# bluetooth.net
KiCad netlist of a schematic drawn in Altium Designer
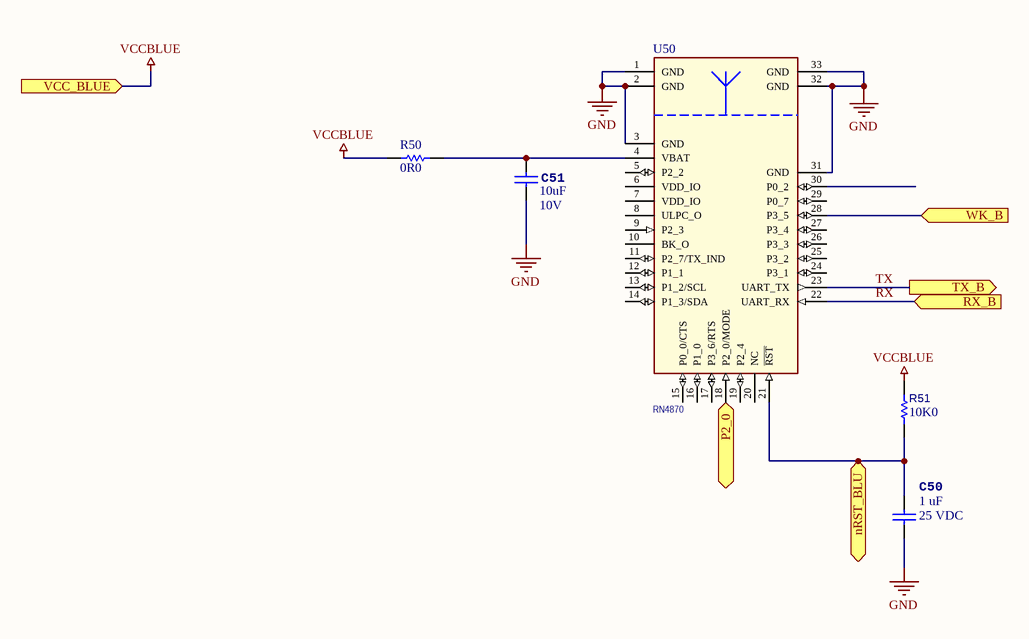
[diagram p0: bluetooth.SchDoc]

(export (version "E")
  (design (tool "Eeschema 10.0.6"))
  (components
    (comp (ref "C50")
      (value "1uF, 25V")
      (footprint "C0603")
      (description "Cap_Cer")
      (fields
        (field (name "MANUFACTURER") "Taiyo Yuden")
        (field (name "MANUFACTURER PART NUMBER") "TMK107BLD105MA-T")
        (field (name "CAPACITANCE") "1 uF")
        (field (name "VOLTAGE RATING DC") "25 VDC")
      )
      (libsource (lib "PULV4") (part "1uF, 25V"))
    )
    (comp (ref "C51")
      (value "ZRB15XR61A106ME01D")
      (footprint "C0402")
      (description "Cap_Cer")
      (fields
        (field (name "MANUFACTURER") "Murata Electronics")
        (field (name "TOLERANCE") "20 %")
        (field (name "CAPACITANCE") "10uF")
        (field (name "VOLTAGE RATING DC") "10V")
      )
      (libsource (lib "PULV5") (part "10uF, 10V"))
    )
    (comp (ref "R50")
      (value "PANASONIC ELECTRONIC COMPONENTS")
      (footprint "0402_RES")
      (description "Resistor")
      (fields (field (name "MANUFACTURER PART NUMBER") "ERJ-2GE0R00X") (field (name "RESISTANCE") "0R0"))
      (libsource (lib "PULV4") (part "0R0"))
    )
    (comp (ref "R51")
      (value "CRCW060310K0FKEB")
      (footprint "RESC0603")
      (description "Resistor")
      (fields
        (field (name "MANUFACTURER") "Vishay / Dale")
        (field (name "TOLERANCE") "1 %")
        (field (name "RESISTANCE") "10K0")
      )
      (libsource (lib "PULV4") (part "10K0,100mW"))
    )
    (comp (ref "U50")
      (value "RN4870")
      (footprint "MOD_BM70BLES1FC2")
      (description "BLUETOOTH")
      (fields
        (field (name "MANUFACTURER") "Microchip Technology")
        (field (name "MANUFACTURER PART NUMBER") "RN4870-I/RM140")
      )
      (libsource (lib "PULV5") (part "579-RN4870-I/RM140"))
    )
  )
  (nets
    (net (code "1") (name "/P2_0") (class "Default")
      (node (ref "U50") (pin "18") (pinfunction "P2_0/MODE_18") (pintype "input"))
    )
    (net (code "2") (name "/RX") (class "Default")
      (node (ref "U50") (pin "22") (pinfunction "UART_RX_22") (pintype "input"))
    )
    (net (code "3") (name "/TX") (class "Default")
      (node (ref "U50") (pin "23") (pinfunction "UART_TX_23") (pintype "output"))
    )
    (net (code "4") (name "/WK_B") (class "Default")
      (node (ref "U50") (pin "28") (pinfunction "P3_5_28") (pintype "bidirectional"))
    )
    (net (code "5") (name "/nRST_BLU") (class "Default")
      (node (ref "C50") (pin "1") (pinfunction "1_1") (pintype "passive"))
      (node (ref "R51") (pin "2") (pinfunction "2_2") (pintype "passive"))
      (node (ref "U50") (pin "21") (pinfunction "~{RST}_21") (pintype "input"))
    )
    (net (code "6") (name "GND") (class "Default")
      (node (ref "C50") (pin "2") (pinfunction "2_2") (pintype "passive"))
      (node (ref "C51") (pin "2") (pinfunction "2_2") (pintype "passive"))
      (node (ref "U50") (pin "1") (pinfunction "GND_1") (pintype "power_in"))
      (node (ref "U50") (pin "2") (pinfunction "GND_2") (pintype "power_in"))
      (node (ref "U50") (pin "3") (pinfunction "GND_3") (pintype "power_in"))
      (node (ref "U50") (pin "31") (pinfunction "GND_31") (pintype "power_in"))
      (node (ref "U50") (pin "32") (pinfunction "GND_32") (pintype "power_in"))
      (node (ref "U50") (pin "33") (pinfunction "GND_33") (pintype "power_in"))
    )
    (net (code "7") (name "Net-(U50-VBAT)") (class "Default")
      (node (ref "C51") (pin "1") (pinfunction "1_1") (pintype "passive"))
      (node (ref "R50") (pin "1") (pinfunction "1_1") (pintype "passive"))
      (node (ref "U50") (pin "4") (pinfunction "VBAT_4") (pintype "power_in"))
    )
    (net (code "8") (name "VCCBLUE") (class "Default")
      (node (ref "R50") (pin "2") (pinfunction "2_2") (pintype "passive"))
      (node (ref "R51") (pin "1") (pinfunction "1_1") (pintype "passive"))
    )
    (net (code "9") (name "unconnected-(U50-BK_O-Pad10)") (class "Default")
      (node (ref "U50") (pin "10") (pinfunction "BK_O_10") (pintype "passive"))
    )
    (net (code "10") (name "unconnected-(U50-NC-Pad20)") (class "Default")
      (node (ref "U50") (pin "20") (pinfunction "NC_20") (pintype "passive"))
    )
    (net (code "11") (name "unconnected-(U50-P0_0{slash}CTS-Pad15)") (class "Default")
      (node (ref "U50") (pin "15") (pinfunction "P0_0/CTS_15") (pintype "bidirectional"))
    )
    (net (code "12") (name "unconnected-(U50-P0_2-Pad30)") (class "Default")
      (node (ref "U50") (pin "30") (pinfunction "P0_2_30") (pintype "bidirectional"))
    )
    (net (code "13") (name "unconnected-(U50-P0_7-Pad29)") (class "Default")
      (node (ref "U50") (pin "29") (pinfunction "P0_7_29") (pintype "bidirectional"))
    )
    (net (code "14") (name "unconnected-(U50-P1_0-Pad16)") (class "Default")
      (node (ref "U50") (pin "16") (pinfunction "P1_0_16") (pintype "bidirectional"))
    )
    (net (code "15") (name "unconnected-(U50-P1_1-Pad12)") (class "Default")
      (node (ref "U50") (pin "12") (pinfunction "P1_1_12") (pintype "bidirectional"))
    )
    (net (code "16") (name "unconnected-(U50-P1_2{slash}SCL-Pad13)") (class "Default")
      (node (ref "U50") (pin "13") (pinfunction "P1_2/SCL_13") (pintype "bidirectional"))
    )
    (net (code "17") (name "unconnected-(U50-P1_3{slash}SDA-Pad14)") (class "Default")
      (node (ref "U50") (pin "14") (pinfunction "P1_3/SDA_14") (pintype "bidirectional"))
    )
    (net (code "18") (name "unconnected-(U50-P2_2-Pad5)") (class "Default")
      (node (ref "U50") (pin "5") (pinfunction "P2_2_5") (pintype "bidirectional"))
    )
    (net (code "19") (name "unconnected-(U50-P2_3-Pad9)") (class "Default")
      (node (ref "U50") (pin "9") (pinfunction "P2_3_9") (pintype "input"))
    )
    (net (code "20") (name "unconnected-(U50-P2_4-Pad19)") (class "Default")
      (node (ref "U50") (pin "19") (pinfunction "P2_4_19") (pintype "bidirectional"))
    )
    (net (code "21") (name "unconnected-(U50-P2_7{slash}TX_IND-Pad11)") (class "Default")
      (node (ref "U50") (pin "11") (pinfunction "P2_7/TX_IND_11") (pintype "bidirectional"))
    )
    (net (code "22") (name "unconnected-(U50-P3_1-Pad24)") (class "Default")
      (node (ref "U50") (pin "24") (pinfunction "P3_1_24") (pintype "bidirectional"))
    )
    (net (code "23") (name "unconnected-(U50-P3_2-Pad25)") (class "Default")
      (node (ref "U50") (pin "25") (pinfunction "P3_2_25") (pintype "bidirectional"))
    )
    (net (code "24") (name "unconnected-(U50-P3_3-Pad26)") (class "Default")
      (node (ref "U50") (pin "26") (pinfunction "P3_3_26") (pintype "bidirectional"))
    )
    (net (code "25") (name "unconnected-(U50-P3_4-Pad27)") (class "Default")
      (node (ref "U50") (pin "27") (pinfunction "P3_4_27") (pintype "bidirectional"))
    )
    (net (code "26") (name "unconnected-(U50-P3_6{slash}RTS-Pad17)") (class "Default")
      (node (ref "U50") (pin "17") (pinfunction "P3_6/RTS_17") (pintype "bidirectional"))
    )
    (net (code "27") (name "unconnected-(U50-ULPC_O-Pad8)") (class "Default")
      (node (ref "U50") (pin "8") (pinfunction "ULPC_O_8") (pintype "passive"))
    )
    (net (code "28") (name "unconnected-(U50-VDD_IO-Pad6)") (class "Default")
      (node (ref "U50") (pin "6") (pinfunction "VDD_IO_6") (pintype "power_in"))
    )
    (net (code "29") (name "unconnected-(U50-VDD_IO-Pad7)") (class "Default")
      (node (ref "U50") (pin "7") (pinfunction "VDD_IO_7") (pintype "power_in"))
    )
  )
)
